# Schematic.net
KiCad netlist of a schematic drawn in Altium Designer
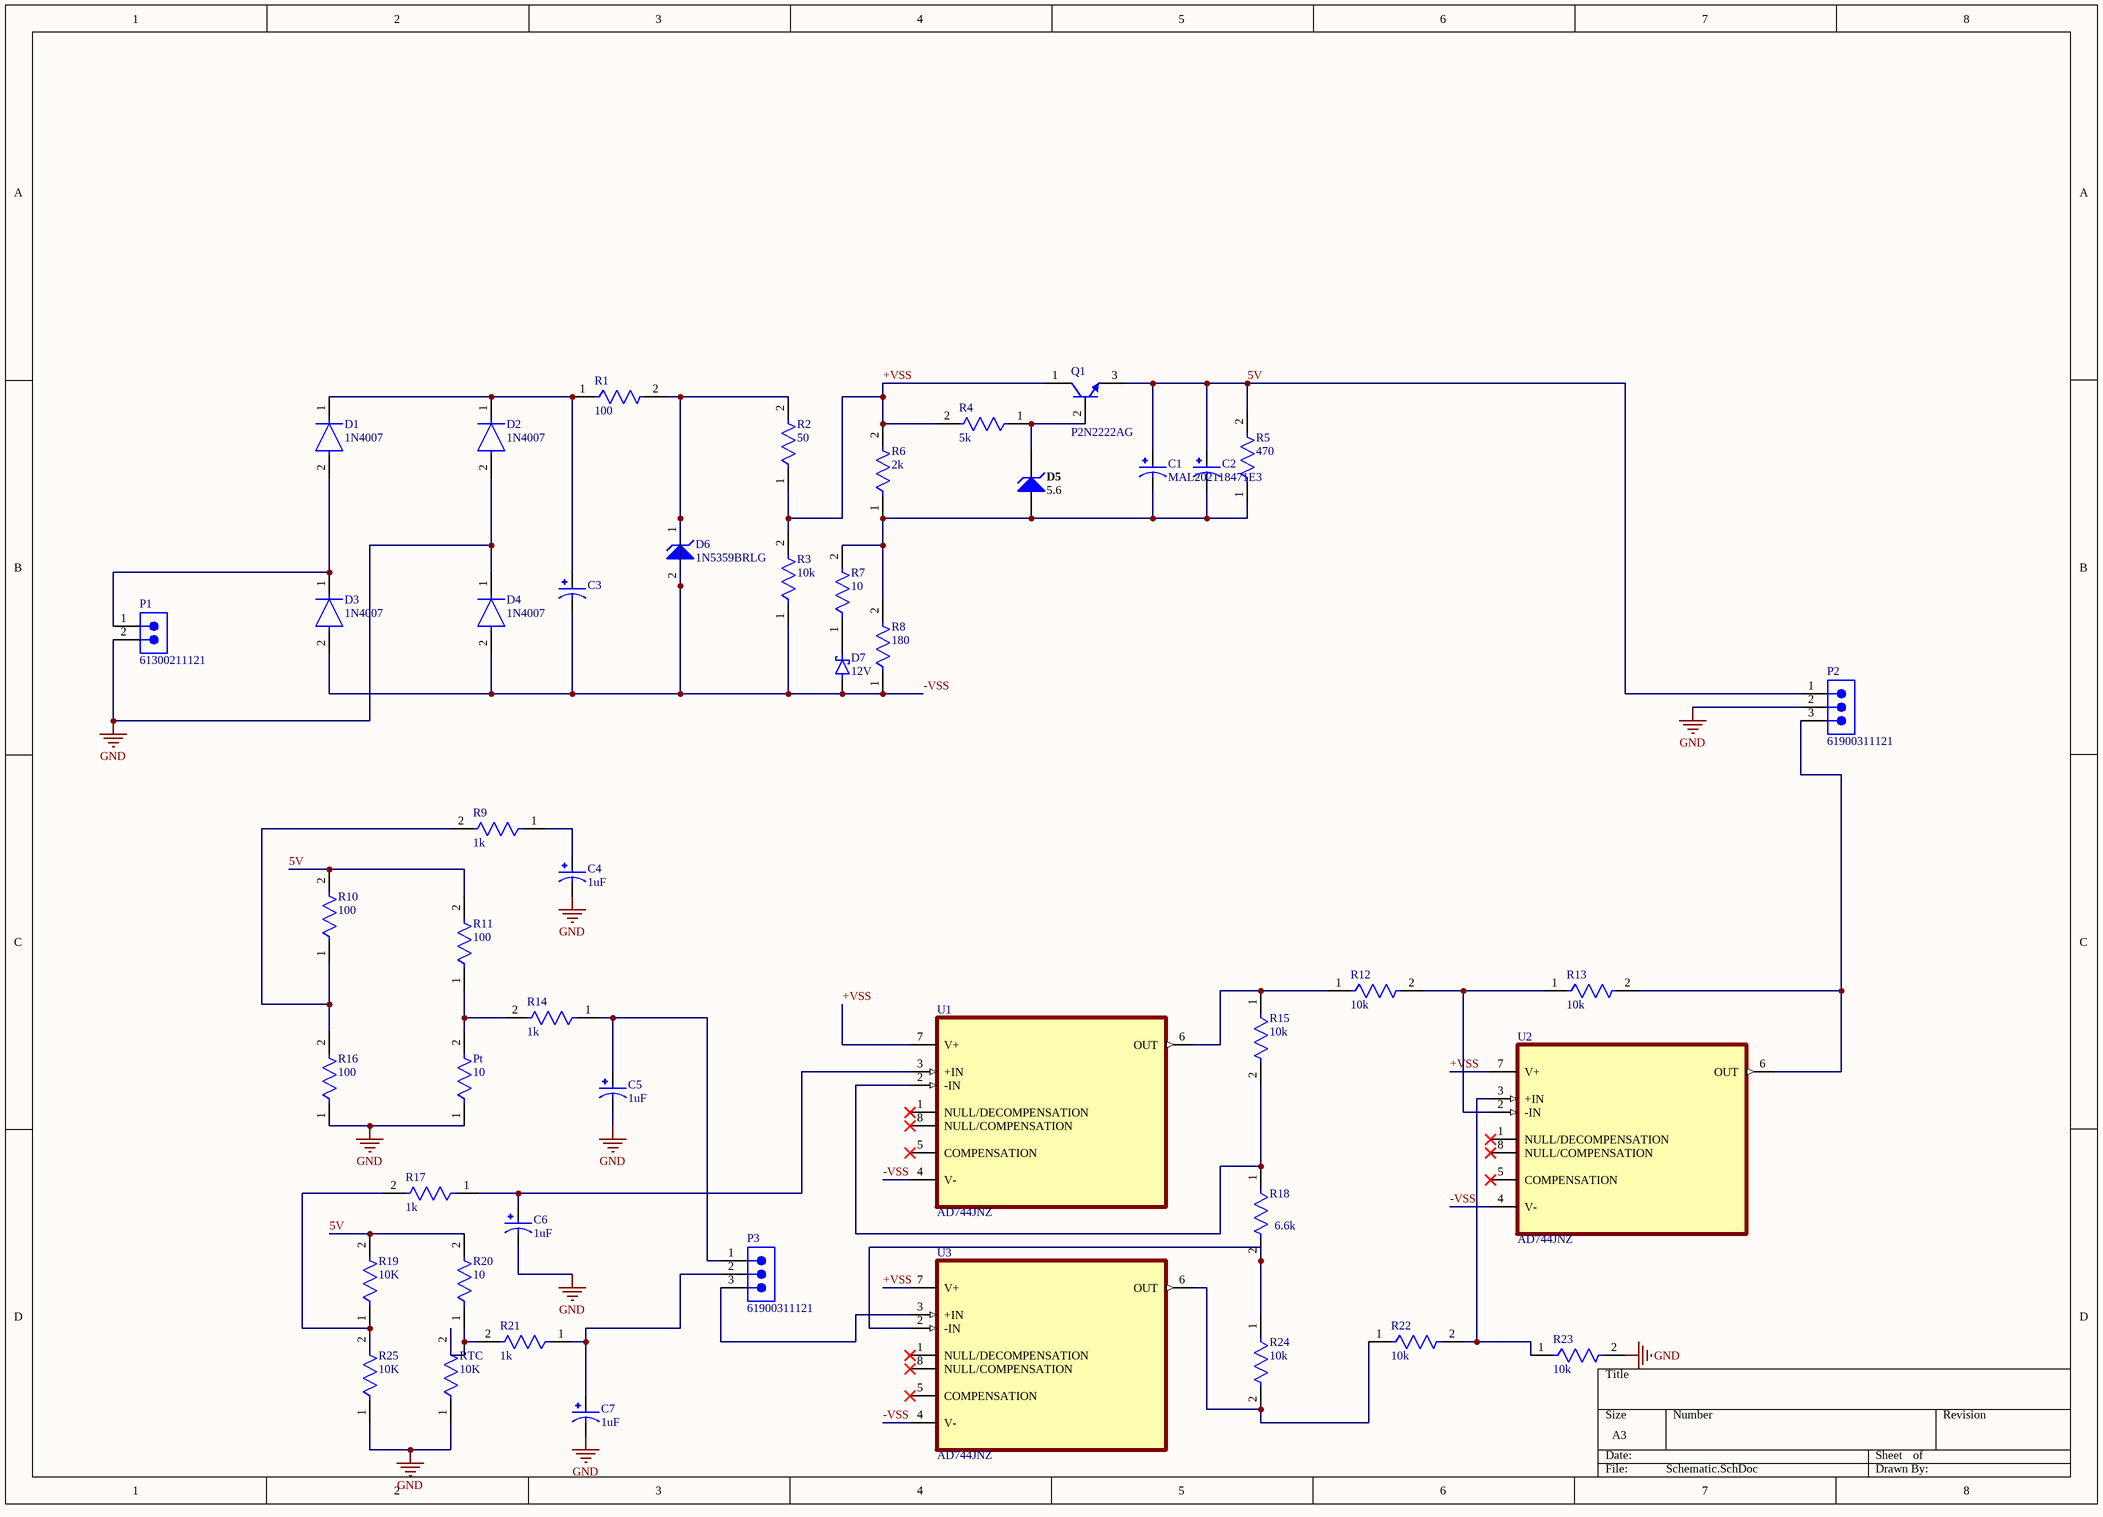
[diagram p0: Schematic.SchDoc]

(export (version "E")
  (design (tool "Eeschema 10.0.6"))
  (components
    (comp (ref "C1")
      (value "MAL202118471E3")
      (footprint "FP-MAL202118471E3-MFG")
      (description "CAP ALUM 470UF 20% 80V RADIAL")
      (fields (field (name "MF") "Panasonic") (field (name "MP") "EEUFS1K471L"))
      (libsource (lib "EEUFS1K471L") (part "EEUFS1K471L"))
    )
    (comp (ref "C2")
      (value "~")
      (footprint "FP-MAL202118471E3-MFG")
      (description "CAP ALUM 470UF 20% 80V RADIAL")
      (fields (field (name "MF") "Panasonic") (field (name "MP") "EEUFS1K471L"))
      (libsource (lib "EEUFS1K471L") (part "EEUFS1K471L"))
    )
    (comp (ref "C3")
      (value "~")
      (footprint "FP-MAL202118471E3-MFG")
      (description "CAP ALUM 470UF 20% 80V RADIAL")
      (fields (field (name "MF") "Panasonic") (field (name "MP") "EEUFS1K471L"))
      (libsource (lib "EEUFS1K471L") (part "EEUFS1K471L"))
    )
    (comp (ref "C4")
      (value "1uF")
      (footprint "FP-MAL202118471E3-MFG")
      (description "CAP ALUM 470UF 20% 80V RADIAL")
      (fields (field (name "MF") "Panasonic") (field (name "MP") "EEUFS1K471L"))
      (libsource (lib "EEUFS1K471L") (part "EEUFS1K471L"))
    )
    (comp (ref "C5")
      (value "1uF")
      (footprint "FP-MAL202118471E3-MFG")
      (description "CAP ALUM 470UF 20% 80V RADIAL")
      (fields (field (name "MF") "Panasonic") (field (name "MP") "EEUFS1K471L"))
      (libsource (lib "EEUFS1K471L") (part "EEUFS1K471L"))
    )
    (comp (ref "C6")
      (value "1uF")
      (footprint "FP-MAL202118471E3-MFG")
      (description "CAP ALUM 470UF 20% 80V RADIAL")
      (fields (field (name "MF") "Panasonic") (field (name "MP") "EEUFS1K471L"))
      (libsource (lib "EEUFS1K471L") (part "EEUFS1K471L"))
    )
    (comp (ref "C7")
      (value "1uF")
      (footprint "FP-MAL202118471E3-MFG")
      (description "CAP ALUM 470UF 20% 80V RADIAL")
      (fields (field (name "MF") "Panasonic") (field (name "MP") "EEUFS1K471L"))
      (libsource (lib "EEUFS1K471L") (part "EEUFS1K471L"))
    )
    (comp (ref "D1")
      (value "1N4007")
      (footprint "FP-1N4007-MFG")
      (description "Rectifier diode 1000 V 1 A DO-41, ,")
      (fields
        (field (name "MANUFACTURER") "Diotec")
        (field (name "OCTOPART") "https://octopart.com/1n4007-diotec-4040411")
      )
      (libsource (lib "Altium Content Vault") (part "d7152d700b627762746794eb795d46e"))
    )
    (comp (ref "D2")
      (value "1N4007")
      (footprint "FP-1N4007-MFG")
      (description "Rectifier diode 1000 V 1 A DO-41, ,")
      (fields
        (field (name "MANUFACTURER") "Diotec")
        (field (name "OCTOPART") "https://octopart.com/1n4007-diotec-4040411")
      )
      (libsource (lib "Altium Content Vault") (part "d7152d700b627762746794eb795d46e"))
    )
    (comp (ref "D3")
      (value "1N4007")
      (footprint "FP-1N4007-MFG")
      (description "Rectifier diode 1000 V 1 A DO-41, ,")
      (fields
        (field (name "MANUFACTURER") "Diotec")
        (field (name "OCTOPART") "https://octopart.com/1n4007-diotec-4040411")
      )
      (libsource (lib "Altium Content Vault") (part "d7152d700b627762746794eb795d46e"))
    )
    (comp (ref "D4")
      (value "1N4007")
      (footprint "FP-1N4007-MFG")
      (description "Rectifier diode 1000 V 1 A DO-41, ,")
      (fields
        (field (name "MANUFACTURER") "Diotec")
        (field (name "OCTOPART") "https://octopart.com/1n4007-diotec-4040411")
      )
      (libsource (lib "Altium Content Vault") (part "d7152d700b627762746794eb795d46e"))
    )
    (comp (ref "D5")
      (value "5.6")
      (footprint "FAIR-DO-41-2_V")
      (description "Zener Diode, 5.6V, 1W, 5%, -65 to 200 degC, 2-Pin DO-41, Body 2.72 x 5.2 mm, RoHS")
      (fields (field (name "MANUFACTURER") "Fairchild Semiconductor") (field (name "TOLERANCE") "5%"))
      (libsource (lib "Altium Content Vault") (part "FAIR-DZEN-A1K2-2"))
    )
    (comp (ref "D6")
      (value "1N5359BRLG")
      (footprint "ONSC-SURMETIC40-2-017AA-01")
      (description "5 W Zener Voltage Regulator, 2-Pin Surmetic(TM) 40, Pb-Free, Tape and Reel")
      (fields (field (name "MANUFACTURER") "On Semiconductor"))
      (libsource (lib "Altium Content Vault") (part "ONSC-K1A2-2"))
    )
    (comp (ref "D7")
      (value "12V")
      (footprint "DIOAD1543W101L863D368")
      (description "Zener Diode Single 12V 5% 2.5Ohm 5000mW 2-Pin Case 017AA-01 T/R")
      (fields (field (name "MF") "ON Semiconductor") (field (name "MP") "1N5349BRL"))
      (libsource (lib "1N5349BRL") (part "1N5349BRL"))
    )
    (comp (ref "P1")
      (value "61300211121")
      (footprint "61300211121")
      (libsource (lib "Altium Content Vault") (part "Header_Male_1R_02P"))
    )
    (comp (ref "P2")
      (value "61900311121")
      (footprint "61900311121")
      (libsource (lib "Altium Content Vault") (part "Header_Male_1R_03P"))
    )
    (comp (ref "P3")
      (value "61900311121")
      (footprint "61900311121")
      (libsource (lib "Altium Content Vault") (part "Header_Male_1R_03P"))
    )
    (comp (ref "Pt")
      (value "10")
      (footprint "FP-MRS25-MFG")
      (fields (field (name "TOLERANCE") "1%"))
      (libsource (lib "Altium Content Vault") (part "1029c3af85768c4190bb7ad29bc67b5"))
    )
    (comp (ref "Q1")
      (value "P2N2222AG")
      (footprint "ONSC-TO-92-3-29-11")
      (description "Amplifier Transistor, NPN Silicon, 3-Pin TO-92, Pb-Free, Bulk Box")
      (fields (field (name "MANUFACTURER") "On Semiconductor"))
      (libsource (lib "Altium Content Vault") (part "ONSC-NPN-C1B2E3-3"))
    )
    (comp (ref "R1")
      (value "100")
      (footprint "FP-MRS25-MFG")
      (fields (field (name "TOLERANCE") "1%"))
      (libsource (lib "Altium Content Vault") (part "1029c3af85768c4190bb7ad29bc67b5"))
    )
    (comp (ref "R2")
      (value "50")
      (footprint "FP-MRS25-MFG")
      (fields (field (name "TOLERANCE") "1%"))
      (libsource (lib "Altium Content Vault") (part "1029c3af85768c4190bb7ad29bc67b5"))
    )
    (comp (ref "R3")
      (value "10k")
      (footprint "FP-MRS25-MFG")
      (fields (field (name "TOLERANCE") "1%"))
      (libsource (lib "Altium Content Vault") (part "1029c3af85768c4190bb7ad29bc67b5"))
    )
    (comp (ref "R4")
      (value "5k")
      (footprint "FP-MRS25-MFG")
      (fields (field (name "TOLERANCE") "1%"))
      (libsource (lib "Altium Content Vault") (part "1029c3af85768c4190bb7ad29bc67b5"))
    )
    (comp (ref "R5")
      (value "470")
      (footprint "FP-MRS25-MFG")
      (fields (field (name "TOLERANCE") "1%"))
      (libsource (lib "Altium Content Vault") (part "1029c3af85768c4190bb7ad29bc67b5"))
    )
    (comp (ref "R6")
      (value "2k")
      (footprint "FP-MRS25-MFG")
      (fields (field (name "TOLERANCE") "1%"))
      (libsource (lib "Altium Content Vault") (part "1029c3af85768c4190bb7ad29bc67b5"))
    )
    (comp (ref "R7")
      (value "10")
      (footprint "FP-MRS25-MFG")
      (fields (field (name "TOLERANCE") "1%"))
      (libsource (lib "Altium Content Vault") (part "1029c3af85768c4190bb7ad29bc67b5"))
    )
    (comp (ref "R8")
      (value "180")
      (footprint "FP-MRS25-MFG")
      (fields (field (name "TOLERANCE") "1%"))
      (libsource (lib "Altium Content Vault") (part "1029c3af85768c4190bb7ad29bc67b5"))
    )
    (comp (ref "R9")
      (value "1k")
      (footprint "FP-MRS25-MFG")
      (fields (field (name "TOLERANCE") "1%"))
      (libsource (lib "Altium Content Vault") (part "1029c3af85768c4190bb7ad29bc67b5"))
    )
    (comp (ref "R10")
      (value "100")
      (footprint "FP-MRS25-MFG")
      (fields (field (name "TOLERANCE") "1%"))
      (libsource (lib "Altium Content Vault") (part "1029c3af85768c4190bb7ad29bc67b5"))
    )
    (comp (ref "R11")
      (value "100")
      (footprint "FP-MRS25-MFG")
      (fields (field (name "TOLERANCE") "1%"))
      (libsource (lib "Altium Content Vault") (part "1029c3af85768c4190bb7ad29bc67b5"))
    )
    (comp (ref "R12")
      (value "10k")
      (footprint "FP-MRS25-MFG")
      (fields (field (name "TOLERANCE") "1%"))
      (libsource (lib "Altium Content Vault") (part "1029c3af85768c4190bb7ad29bc67b5"))
    )
    (comp (ref "R13")
      (value "10k")
      (footprint "FP-MRS25-MFG")
      (fields (field (name "TOLERANCE") "1%"))
      (libsource (lib "Altium Content Vault") (part "1029c3af85768c4190bb7ad29bc67b5"))
    )
    (comp (ref "R14")
      (value "1k")
      (footprint "FP-MRS25-MFG")
      (fields (field (name "TOLERANCE") "1%"))
      (libsource (lib "Altium Content Vault") (part "1029c3af85768c4190bb7ad29bc67b5"))
    )
    (comp (ref "R15")
      (value "10k")
      (footprint "FP-MRS25-MFG")
      (fields (field (name "TOLERANCE") "1%"))
      (libsource (lib "Altium Content Vault") (part "1029c3af85768c4190bb7ad29bc67b5"))
    )
    (comp (ref "R16")
      (value "100")
      (footprint "FP-MRS25-MFG")
      (fields (field (name "TOLERANCE") "1%"))
      (libsource (lib "Altium Content Vault") (part "1029c3af85768c4190bb7ad29bc67b5"))
    )
    (comp (ref "R17")
      (value "1k")
      (footprint "FP-MRS25-MFG")
      (fields (field (name "TOLERANCE") "1%"))
      (libsource (lib "Altium Content Vault") (part "1029c3af85768c4190bb7ad29bc67b5"))
    )
    (comp (ref "R18")
      (value "6.6k")
      (footprint "FP-MRS25-MFG")
      (fields (field (name "TOLERANCE") "1%"))
      (libsource (lib "Altium Content Vault") (part "1029c3af85768c4190bb7ad29bc67b5"))
    )
    (comp (ref "R19")
      (value "10K")
      (footprint "FP-MRS25-MFG")
      (fields (field (name "TOLERANCE") "1%"))
      (libsource (lib "Altium Content Vault") (part "1029c3af85768c4190bb7ad29bc67b5"))
    )
    (comp (ref "R20")
      (value "10")
      (footprint "FP-MRS25-MFG")
      (fields (field (name "TOLERANCE") "1%"))
      (libsource (lib "Altium Content Vault") (part "1029c3af85768c4190bb7ad29bc67b5"))
    )
    (comp (ref "R21")
      (value "1k")
      (footprint "FP-MRS25-MFG")
      (fields (field (name "TOLERANCE") "1%"))
      (libsource (lib "Altium Content Vault") (part "1029c3af85768c4190bb7ad29bc67b5"))
    )
    (comp (ref "R22")
      (value "10k")
      (footprint "FP-MRS25-MFG")
      (fields (field (name "TOLERANCE") "1%"))
      (libsource (lib "Altium Content Vault") (part "1029c3af85768c4190bb7ad29bc67b5"))
    )
    (comp (ref "R23")
      (value "10k")
      (footprint "FP-MRS25-MFG")
      (fields (field (name "TOLERANCE") "1%"))
      (libsource (lib "Altium Content Vault") (part "1029c3af85768c4190bb7ad29bc67b5"))
    )
    (comp (ref "R24")
      (value "10k")
      (footprint "FP-MRS25-MFG")
      (fields (field (name "TOLERANCE") "1%"))
      (libsource (lib "Altium Content Vault") (part "1029c3af85768c4190bb7ad29bc67b5"))
    )
    (comp (ref "R25")
      (value "10K")
      (footprint "FP-MRS25-MFG")
      (fields (field (name "TOLERANCE") "1%"))
      (libsource (lib "Altium Content Vault") (part "1029c3af85768c4190bb7ad29bc67b5"))
    )
    (comp (ref "RTC")
      (value "10K")
      (footprint "FP-MRS25-MFG")
      (fields (field (name "TOLERANCE") "1%"))
      (libsource (lib "Altium Content Vault") (part "1029c3af85768c4190bb7ad29bc67b5"))
    )
    (comp (ref "U1")
      (value "AD744JNZ")
      (footprint "DIP254P762X444-8")
      (description "Precision, 500 ns Settling BiFET Op Amp")
      (fields (field (name "MF") "Analog Devices"))
      (libsource (lib "AD744JNZ") (part "AD744JNZ"))
    )
    (comp (ref "U2")
      (value "AD744JNZ")
      (footprint "DIP254P762X444-8")
      (description "Precision, 500 ns Settling BiFET Op Amp")
      (fields (field (name "MF") "Analog Devices"))
      (libsource (lib "AD744JNZ") (part "AD744JNZ"))
    )
    (comp (ref "U3")
      (value "AD744JNZ")
      (footprint "DIP254P762X444-8")
      (description "Precision, 500 ns Settling BiFET Op Amp")
      (fields (field (name "MF") "Analog Devices"))
      (libsource (lib "AD744JNZ") (part "AD744JNZ"))
    )
  )
  (nets
    (net (code "1") (name "/+VSS") (class "Default")
      (node (ref "Q1") (pin "1") (pinfunction "C_1") (pintype "passive"))
      (node (ref "R2") (pin "1") (pinfunction "1_1") (pintype "passive"))
      (node (ref "R3") (pin "2") (pinfunction "2_2") (pintype "passive"))
      (node (ref "R4") (pin "2") (pinfunction "2_2") (pintype "passive"))
      (node (ref "R6") (pin "2") (pinfunction "2_2") (pintype "passive"))
      (node (ref "U1") (pin "7") (pinfunction "V+_7") (pintype "power_in"))
      (node (ref "U2") (pin "7") (pinfunction "V+_7") (pintype "power_in"))
      (node (ref "U3") (pin "7") (pinfunction "V+_7") (pintype "power_in"))
    )
    (net (code "2") (name "/-VSS") (class "Default")
      (node (ref "C3") (pin "N") (pinfunction "N_N") (pintype "passive"))
      (node (ref "D3") (pin "2") (pinfunction "A_2") (pintype "passive"))
      (node (ref "D4") (pin "2") (pinfunction "A_2") (pintype "passive"))
      (node (ref "D6") (pin "1") (pinfunction "K_1") (pintype "passive"))
      (node (ref "D6") (pin "2") (pinfunction "A_2") (pintype "passive"))
      (node (ref "D7") (pin "2") (pinfunction "A_2") (pintype "passive"))
      (node (ref "R1") (pin "2") (pinfunction "2_2") (pintype "passive"))
      (node (ref "R2") (pin "2") (pinfunction "2_2") (pintype "passive"))
      (node (ref "R3") (pin "1") (pinfunction "1_1") (pintype "passive"))
      (node (ref "R8") (pin "1") (pinfunction "1_1") (pintype "passive"))
      (node (ref "U1") (pin "4") (pinfunction "V-_4") (pintype "power_in"))
      (node (ref "U2") (pin "4") (pinfunction "V-_4") (pintype "power_in"))
      (node (ref "U3") (pin "4") (pinfunction "V-_4") (pintype "power_in"))
    )
    (net (code "3") (name "/5V") (class "Default")
      (node (ref "C1") (pin "P") (pinfunction "P_P") (pintype "passive"))
      (node (ref "C2") (pin "P") (pinfunction "P_P") (pintype "passive"))
      (node (ref "P2") (pin "1") (pinfunction "1_1") (pintype "passive"))
      (node (ref "Q1") (pin "3") (pinfunction "E_3") (pintype "passive"))
      (node (ref "R10") (pin "2") (pinfunction "2_2") (pintype "passive"))
      (node (ref "R11") (pin "2") (pinfunction "2_2") (pintype "passive"))
      (node (ref "R19") (pin "2") (pinfunction "2_2") (pintype "passive"))
      (node (ref "R20") (pin "2") (pinfunction "2_2") (pintype "passive"))
      (node (ref "R5") (pin "2") (pinfunction "2_2") (pintype "passive"))
    )
    (net (code "4") (name "GND") (class "Default")
      (node (ref "C4") (pin "N") (pinfunction "N_N") (pintype "passive"))
      (node (ref "C5") (pin "N") (pinfunction "N_N") (pintype "passive"))
      (node (ref "C6") (pin "N") (pinfunction "N_N") (pintype "passive"))
      (node (ref "C7") (pin "N") (pinfunction "N_N") (pintype "passive"))
      (node (ref "D2") (pin "2") (pinfunction "A_2") (pintype "passive"))
      (node (ref "D4") (pin "1") (pinfunction "C_1") (pintype "passive"))
      (node (ref "P1") (pin "2") (pinfunction "2_2") (pintype "passive"))
      (node (ref "P2") (pin "2") (pinfunction "2_2") (pintype "passive"))
      (node (ref "Pt") (pin "1") (pinfunction "1_1") (pintype "passive"))
      (node (ref "R16") (pin "1") (pinfunction "1_1") (pintype "passive"))
      (node (ref "R23") (pin "2") (pinfunction "2_2") (pintype "passive"))
      (node (ref "R25") (pin "1") (pinfunction "1_1") (pintype "passive"))
      (node (ref "RTC") (pin "1") (pinfunction "1_1") (pintype "passive"))
    )
    (net (code "5") (name "Net-(C4-PadP)") (class "Default")
      (node (ref "C4") (pin "P") (pinfunction "P_P") (pintype "passive"))
      (node (ref "R9") (pin "1") (pinfunction "1_1") (pintype "passive"))
    )
    (net (code "6") (name "Net-(C5-PadP)") (class "Default")
      (node (ref "C5") (pin "P") (pinfunction "P_P") (pintype "passive"))
      (node (ref "P3") (pin "1") (pinfunction "1_1") (pintype "passive"))
      (node (ref "R14") (pin "1") (pinfunction "1_1") (pintype "passive"))
    )
    (net (code "7") (name "Net-(C7-PadP)") (class "Default")
      (node (ref "C7") (pin "P") (pinfunction "P_P") (pintype "passive"))
      (node (ref "P3") (pin "2") (pinfunction "2_2") (pintype "passive"))
      (node (ref "R21") (pin "1") (pinfunction "1_1") (pintype "passive"))
    )
    (net (code "8") (name "Net-(D1-A)") (class "Default")
      (node (ref "D1") (pin "2") (pinfunction "A_2") (pintype "passive"))
      (node (ref "D3") (pin "1") (pinfunction "C_1") (pintype "passive"))
      (node (ref "P1") (pin "1") (pinfunction "1_1") (pintype "passive"))
    )
    (net (code "9") (name "Net-(D1-C)") (class "Default")
      (node (ref "C3") (pin "P") (pinfunction "P_P") (pintype "passive"))
      (node (ref "D1") (pin "1") (pinfunction "C_1") (pintype "passive"))
      (node (ref "D2") (pin "1") (pinfunction "C_1") (pintype "passive"))
      (node (ref "R1") (pin "1") (pinfunction "1_1") (pintype "passive"))
    )
    (net (code "10") (name "Net-(D5-A)") (class "Default")
      (node (ref "C1") (pin "N") (pinfunction "N_N") (pintype "passive"))
      (node (ref "C2") (pin "N") (pinfunction "N_N") (pintype "passive"))
      (node (ref "D5") (pin "1") (pinfunction "A_1") (pintype "passive"))
      (node (ref "R5") (pin "1") (pinfunction "1_1") (pintype "passive"))
      (node (ref "R6") (pin "1") (pinfunction "1_1") (pintype "passive"))
      (node (ref "R7") (pin "2") (pinfunction "2_2") (pintype "passive"))
      (node (ref "R8") (pin "2") (pinfunction "2_2") (pintype "passive"))
    )
    (net (code "11") (name "Net-(D5-K)") (class "Default")
      (node (ref "D5") (pin "2") (pinfunction "K_2") (pintype "passive"))
      (node (ref "Q1") (pin "2") (pinfunction "B_2") (pintype "passive"))
      (node (ref "R4") (pin "1") (pinfunction "1_1") (pintype "passive"))
    )
    (net (code "12") (name "Net-(D7-K)") (class "Default")
      (node (ref "D7") (pin "1") (pinfunction "K_1") (pintype "passive"))
      (node (ref "R7") (pin "1") (pinfunction "1_1") (pintype "passive"))
    )
    (net (code "13") (name "Net-(Pt-Pad2)") (class "Default")
      (node (ref "Pt") (pin "2") (pinfunction "2_2") (pintype "passive"))
      (node (ref "R11") (pin "1") (pinfunction "1_1") (pintype "passive"))
      (node (ref "R14") (pin "2") (pinfunction "2_2") (pintype "passive"))
    )
    (net (code "14") (name "Net-(R10-Pad1)") (class "Default")
      (node (ref "R10") (pin "1") (pinfunction "1_1") (pintype "passive"))
      (node (ref "R16") (pin "2") (pinfunction "2_2") (pintype "passive"))
      (node (ref "R9") (pin "2") (pinfunction "2_2") (pintype "passive"))
    )
    (net (code "15") (name "Net-(R17-Pad2)") (class "Default")
      (node (ref "R17") (pin "2") (pinfunction "2_2") (pintype "passive"))
      (node (ref "R19") (pin "1") (pinfunction "1_1") (pintype "passive"))
      (node (ref "R25") (pin "2") (pinfunction "2_2") (pintype "passive"))
    )
    (net (code "16") (name "Net-(R20-Pad1)") (class "Default")
      (node (ref "R20") (pin "1") (pinfunction "1_1") (pintype "passive"))
      (node (ref "R21") (pin "2") (pinfunction "2_2") (pintype "passive"))
      (node (ref "RTC") (pin "2") (pinfunction "2_2") (pintype "passive"))
    )
    (net (code "17") (name "Net-(U1-+IN)") (class "Default")
      (node (ref "C6") (pin "P") (pinfunction "P_P") (pintype "passive"))
      (node (ref "R17") (pin "1") (pinfunction "1_1") (pintype "passive"))
      (node (ref "U1") (pin "3") (pinfunction "+IN_3") (pintype "input"))
    )
    (net (code "18") (name "Net-(U1--IN)") (class "Default")
      (node (ref "R15") (pin "2") (pinfunction "2_2") (pintype "passive"))
      (node (ref "R18") (pin "1") (pinfunction "1_1") (pintype "passive"))
      (node (ref "U1") (pin "2") (pinfunction "-IN_2") (pintype "input"))
    )
    (net (code "19") (name "Net-(U1-OUT)") (class "Default")
      (node (ref "R12") (pin "1") (pinfunction "1_1") (pintype "passive"))
      (node (ref "R15") (pin "1") (pinfunction "1_1") (pintype "passive"))
      (node (ref "U1") (pin "6") (pinfunction "OUT_6") (pintype "output"))
    )
    (net (code "20") (name "Net-(U2-+IN)") (class "Default")
      (node (ref "R22") (pin "2") (pinfunction "2_2") (pintype "passive"))
      (node (ref "R23") (pin "1") (pinfunction "1_1") (pintype "passive"))
      (node (ref "U2") (pin "3") (pinfunction "+IN_3") (pintype "input"))
    )
    (net (code "21") (name "Net-(U2--IN)") (class "Default")
      (node (ref "R12") (pin "2") (pinfunction "2_2") (pintype "passive"))
      (node (ref "R13") (pin "1") (pinfunction "1_1") (pintype "passive"))
      (node (ref "U2") (pin "2") (pinfunction "-IN_2") (pintype "input"))
    )
    (net (code "22") (name "Net-(U2-OUT)") (class "Default")
      (node (ref "P2") (pin "3") (pinfunction "3_3") (pintype "passive"))
      (node (ref "R13") (pin "2") (pinfunction "2_2") (pintype "passive"))
      (node (ref "U2") (pin "6") (pinfunction "OUT_6") (pintype "output"))
    )
    (net (code "23") (name "Net-(U3-+IN)") (class "Default")
      (node (ref "P3") (pin "3") (pinfunction "3_3") (pintype "passive"))
      (node (ref "U3") (pin "3") (pinfunction "+IN_3") (pintype "input"))
    )
    (net (code "24") (name "Net-(U3--IN)") (class "Default")
      (node (ref "R18") (pin "2") (pinfunction "2_2") (pintype "passive"))
      (node (ref "R24") (pin "1") (pinfunction "1_1") (pintype "passive"))
      (node (ref "U3") (pin "2") (pinfunction "-IN_2") (pintype "input"))
    )
    (net (code "25") (name "Net-(U3-OUT)") (class "Default")
      (node (ref "R22") (pin "1") (pinfunction "1_1") (pintype "passive"))
      (node (ref "R24") (pin "2") (pinfunction "2_2") (pintype "passive"))
      (node (ref "U3") (pin "6") (pinfunction "OUT_6") (pintype "output"))
    )
    (net (code "26") (name "unconnected-(U1-COMPENSATION-Pad5)") (class "Default")
      (node (ref "U1") (pin "5") (pinfunction "COMPENSATION_5") (pintype "passive+no_connect"))
    )
    (net (code "27") (name "unconnected-(U1-NULL{slash}COMPENSATION-Pad8)") (class "Default")
      (node (ref "U1") (pin "8") (pinfunction "NULL/COMPENSATION_8") (pintype "passive+no_connect"))
    )
    (net (code "28") (name "unconnected-(U1-NULL{slash}DECOMPENSATION-Pad1)") (class "Default")
      (node (ref "U1") (pin "1") (pinfunction "NULL/DECOMPENSATION_1") (pintype "passive+no_connect"))
    )
    (net (code "29") (name "unconnected-(U2-COMPENSATION-Pad5)") (class "Default")
      (node (ref "U2") (pin "5") (pinfunction "COMPENSATION_5") (pintype "passive+no_connect"))
    )
    (net (code "30") (name "unconnected-(U2-NULL{slash}COMPENSATION-Pad8)") (class "Default")
      (node (ref "U2") (pin "8") (pinfunction "NULL/COMPENSATION_8") (pintype "passive+no_connect"))
    )
    (net (code "31") (name "unconnected-(U2-NULL{slash}DECOMPENSATION-Pad1)") (class "Default")
      (node (ref "U2") (pin "1") (pinfunction "NULL/DECOMPENSATION_1") (pintype "passive+no_connect"))
    )
    (net (code "32") (name "unconnected-(U3-COMPENSATION-Pad5)") (class "Default")
      (node (ref "U3") (pin "5") (pinfunction "COMPENSATION_5") (pintype "passive+no_connect"))
    )
    (net (code "33") (name "unconnected-(U3-NULL{slash}COMPENSATION-Pad8)") (class "Default")
      (node (ref "U3") (pin "8") (pinfunction "NULL/COMPENSATION_8") (pintype "passive+no_connect"))
    )
    (net (code "34") (name "unconnected-(U3-NULL{slash}DECOMPENSATION-Pad1)") (class "Default")
      (node (ref "U3") (pin "1") (pinfunction "NULL/DECOMPENSATION_1") (pintype "passive+no_connect"))
    )
  )
)
